# 3_3V_Regulator.net
KiCad netlist of a schematic drawn in Altium Designer
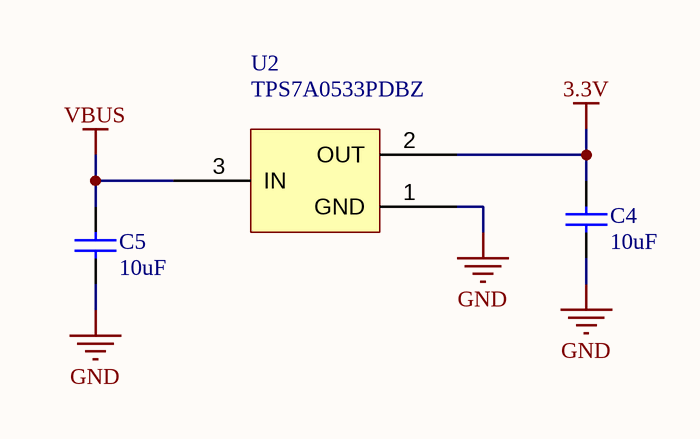
[diagram p0: 3.3V Regulator.SchDoc]

(export (version "E")
  (design (tool "Eeschema 10.0.6"))
  (components
    (comp (ref "C4") (value "10uF") (footprint "Capacitor 0402") (libsource (lib "x-io") (part "Capacitor")))
    (comp (ref "C5") (value "10uF") (footprint "Capacitor 0402") (libsource (lib "x-io") (part "Capacitor")))
    (comp (ref "U2")
      (value "TPS7A0533PDBZ")
      (footprint "SOT-23")
      (libsource (lib "x-io") (part "TPS7A0533PDBZ"))
    )
  )
  (nets
    (net (code "1") (name "3.3V") (class "Default")
      (node (ref "C4") (pin "2") (pinfunction "2_2") (pintype "passive"))
      (node (ref "U2") (pin "2") (pinfunction "OUT_2") (pintype "passive"))
    )
    (net (code "2") (name "GND") (class "Default")
      (node (ref "C4") (pin "1") (pinfunction "1_1") (pintype "passive"))
      (node (ref "C5") (pin "1") (pinfunction "1_1") (pintype "passive"))
      (node (ref "U2") (pin "1") (pinfunction "GND_1") (pintype "passive"))
    )
    (net (code "3") (name "VBUS") (class "Default")
      (node (ref "C5") (pin "2") (pinfunction "2_2") (pintype "passive"))
      (node (ref "U2") (pin "3") (pinfunction "IN_3") (pintype "passive"))
    )
  )
)
